# CH32V205CCT-R0.net
KiCad netlist of a schematic drawn in Altium Designer
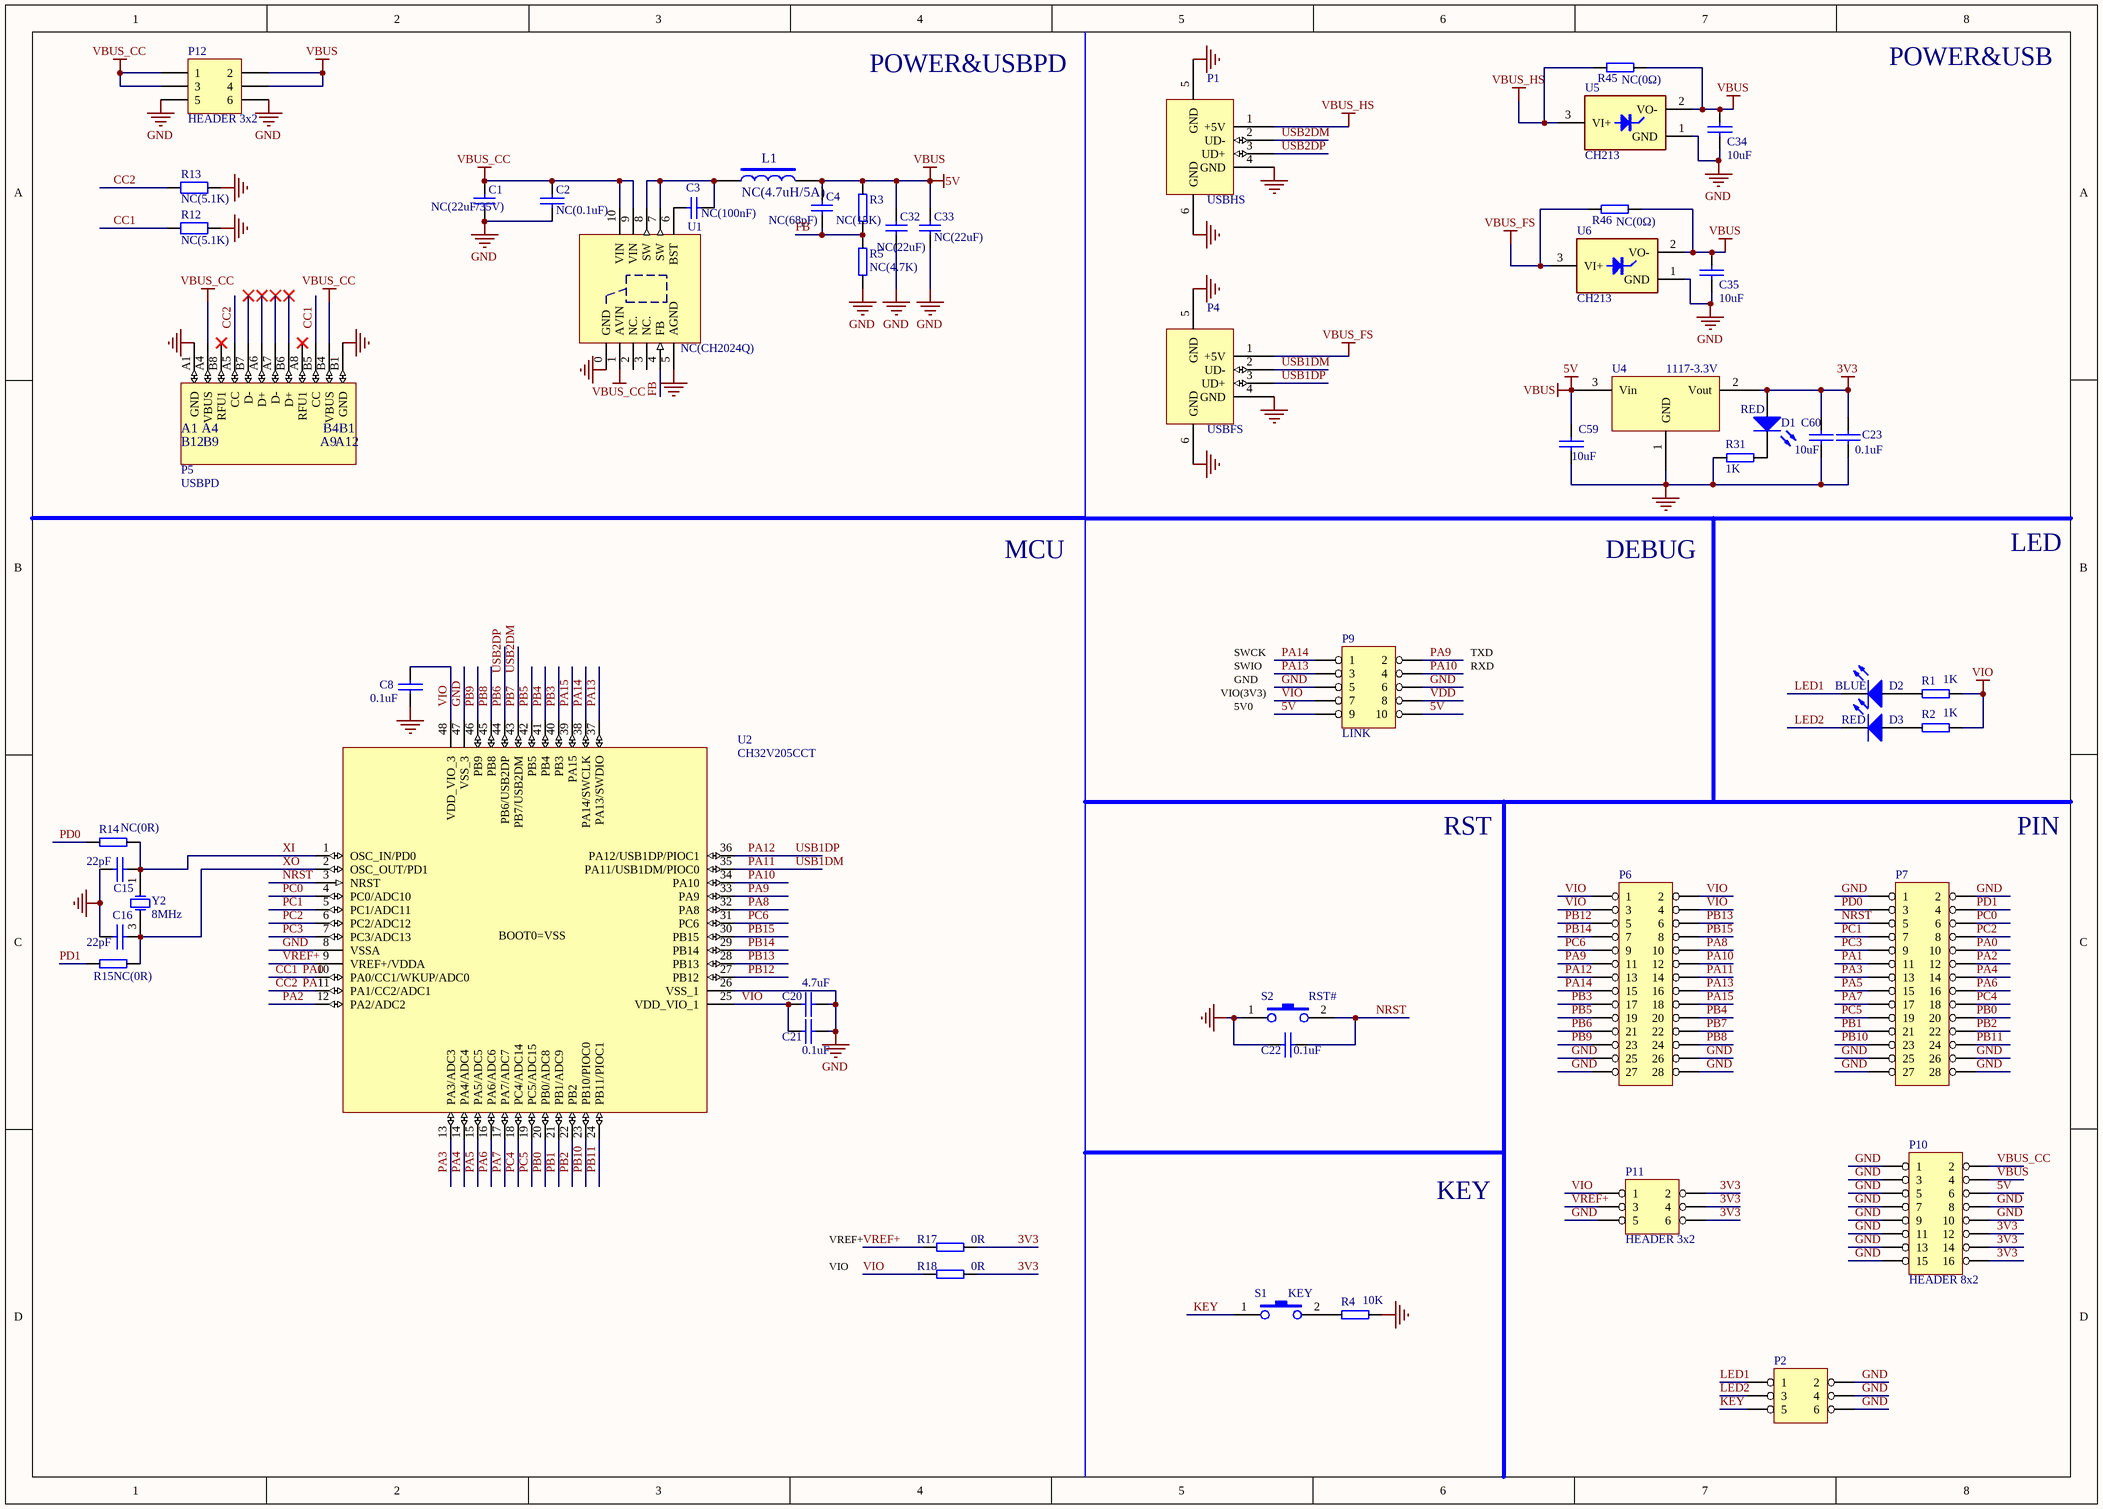
[diagram p0: CH32V205CCT-R0.SchDoc]

(export (version "E")
  (design (tool "Eeschema 10.0.6"))
  (components
    (comp (ref "C1")
      (value "NC(22uF/35V)")
      (footprint "0805_C")
      (description "贴片电容")
      (libsource (lib "Miscellaneous Devices LC") (part "0603 100nF (104) 10% 50V"))
    )
    (comp (ref "C2")
      (value "NC(0.1uF)")
      (footprint "0402_C")
      (description "Capacitor")
      (libsource (lib "*") (part "CAP"))
    )
    (comp (ref "C3")
      (value "NC(100nF)")
      (footprint "0603_C")
      (description "贴片电容")
      (libsource (lib "Miscellaneous Devices LC") (part "0603 1uF (105) 10% 50V"))
    )
    (comp (ref "C4")
      (value "NC(68pF)")
      (footprint "0402_C")
      (description "贴片电容")
      (libsource (lib "Miscellaneous Devices LC") (part "0603 100nF (104) 10% 50V"))
    )
    (comp (ref "C8")
      (value "0.1uF")
      (footprint "0603_C")
      (description "Capacitor")
      (libsource (lib "*") (part "CAP"))
    )
    (comp (ref "C15")
      (value "22pF")
      (footprint "0603_C")
      (description "Capacitor")
      (libsource (lib "*") (part "CAP"))
    )
    (comp (ref "C16")
      (value "22pF")
      (footprint "0603_C")
      (description "Capacitor")
      (libsource (lib "*") (part "CAP"))
    )
    (comp (ref "C20")
      (value "4.7uF")
      (footprint "0603_C")
      (description "Capacitor")
      (libsource (lib "*") (part "CAP"))
    )
    (comp (ref "C21")
      (value "0.1uF")
      (footprint "0603_C")
      (description "Capacitor")
      (libsource (lib "*") (part "CAP"))
    )
    (comp (ref "C22")
      (value "0.1uF")
      (footprint "0603_C")
      (description "Capacitor")
      (libsource (lib "") (part "CAP_1"))
    )
    (comp (ref "C23")
      (value "0.1uF")
      (footprint "0402_C")
      (description "Capacitor")
      (libsource (lib "*") (part "CAP"))
    )
    (comp (ref "C32")
      (value "NC(22uF)")
      (footprint "0805_C")
      (description "贴片电容")
      (libsource (lib "Miscellaneous Devices LC") (part "0603 100nF (104) 10% 50V"))
    )
    (comp (ref "C33")
      (value "NC(22uF)")
      (footprint "0805_C")
      (description "贴片电容")
      (libsource (lib "Miscellaneous Devices LC") (part "0603 100nF (104) 10% 50V"))
    )
    (comp (ref "C34")
      (value "10uF")
      (footprint "0603_C")
      (description "Capacitor")
      (libsource (lib "") (part "CAP_1"))
    )
    (comp (ref "C35")
      (value "10uF")
      (footprint "0603_C")
      (description "Capacitor")
      (libsource (lib "") (part "CAP_1"))
    )
    (comp (ref "C59")
      (value "10uF")
      (footprint "0603_C")
      (description "Capacitor")
      (libsource (lib "*") (part "CAP"))
    )
    (comp (ref "C60")
      (value "10uF")
      (footprint "0603_C")
      (description "Capacitor")
      (libsource (lib "*") (part "CAP"))
    )
    (comp (ref "D1")
      (value "RED")
      (footprint "0603+")
      (description "Typical INFRARED GaAs LED")
      (fields (field (name "PUBLISHER") "Altium Limited"))
      (libsource (lib "*") (part "LED0"))
    )
    (comp (ref "D2")
      (value "BLUE")
      (footprint "0603+")
      (description "Typical INFRARED GaAs LED")
      (fields (field (name "PUBLISHER") "Altium Limited"))
      (libsource (lib "*") (part "LED0"))
    )
    (comp (ref "D3")
      (value "RED")
      (footprint "0603+")
      (description "Typical INFRARED GaAs LED")
      (fields (field (name "PUBLISHER") "Altium Limited"))
      (libsource (lib "*") (part "LED0"))
    )
    (comp (ref "L1")
      (value "NC(4.7uH/5A)")
      (footprint "SMD_6x6mm")
      (libsource (lib "wch_sch_others") (part "INDUCTOR"))
    )
    (comp (ref "P1")
      (value "USBHS")
      (footprint "USBAF")
      (description "USB Port")
      (libsource (lib "*") (part "USB"))
    )
    (comp (ref "P2")
      (value "IO")
      (footprint "MYPCB:IDC6-2.54mm")
      (description "Header, 3-Pin, Dual row")
      (libsource (lib "") (part "HEADER 3x2_1"))
    )
    (comp (ref "P4")
      (value "USBFS")
      (footprint "USBAF")
      (description "USB Port")
      (libsource (lib "*") (part "USB"))
    )
    (comp (ref "P5")
      (value "USBPD")
      (footprint "TYPE-C-Receptacle-2.0")
      (libsource (lib "*") (part "TYPE-C1"))
    )
    (comp (ref "P6")
      (value "~")
      (footprint "MYPCB:IDC28-2.54MM")
      (description "Header, 14-Pin, Dual row")
      (libsource (lib "wch_sch_others") (part "HEADER 14x2"))
    )
    (comp (ref "P7")
      (value "~")
      (footprint "MYPCB:IDC28-2.54MM")
      (description "Header, 14-Pin, Dual row")
      (libsource (lib "wch_sch_others") (part "HEADER 14x2"))
    )
    (comp (ref "P9")
      (value "LINK")
      (footprint "MYPCB:IDC10-2.54mm")
      (description "Header, 5-Pin, Dual row")
      (libsource (lib "wch_sch_others") (part "HEADER 5x2"))
    )
    (comp (ref "P10")
      (value "HEADER 8x2")
      (footprint "MYPCB:IDC16-2.54mm")
      (description "Header, 8-Pin, Dual row")
      (libsource (lib "wch_sch_others") (part "HEADER 8x2"))
    )
    (comp (ref "P11")
      (value "HEADER 3x2")
      (footprint "MYPCB:IDC6-2.54mm")
      (description "Header, 3-Pin, Dual row")
      (libsource (lib "") (part "HEADER 3x2_1"))
    )
    (comp (ref "P12")
      (value "HEADER 3x2")
      (footprint "MYPCB:IDC6-2.54mm")
      (description "Header, 3-Pin, Dual row")
      (libsource (lib "wch_sch_others") (part "HEADER 3x2"))
    )
    (comp (ref "R1") (value "1K") (footprint "CHXXX:0603") (libsource (lib "wch_sch_others") (part "RES")))
    (comp (ref "R2") (value "1K") (footprint "CHXXX:0603") (libsource (lib "wch_sch_others") (part "RES")))
    (comp (ref "R3") (value "NC(15K)") (footprint "0402") (libsource (lib "wch_sch_others(1)") (part "RES")))
    (comp (ref "R4") (value "10K") (footprint "CHXXX:0603") (libsource (lib "wch_sch_others") (part "RES")))
    (comp (ref "R5") (value "NC(4.7K)") (footprint "0402") (libsource (lib "wch_sch_others(1)") (part "RES")))
    (comp (ref "R12")
      (value "NC(5.1K)")
      (footprint "0402")
      (description "Resistor")
      (libsource (lib "Miscellaneous Devices") (part "Res2"))
    )
    (comp (ref "R13")
      (value "NC(5.1K)")
      (footprint "0402")
      (description "Resistor")
      (libsource (lib "Miscellaneous Devices") (part "Res2"))
    )
    (comp (ref "R14")
      (value "NC(0R)")
      (footprint "CHXXX:0603")
      (libsource (lib "wch_sch_others") (part "RES"))
    )
    (comp (ref "R15")
      (value "NC(0R)")
      (footprint "CHXXX:0603")
      (libsource (lib "wch_sch_others") (part "RES"))
    )
    (comp (ref "R17") (value "0R") (footprint "CHXXX:0603") (libsource (lib "*") (part "R")))
    (comp (ref "R18") (value "0R") (footprint "CHXXX:0603") (libsource (lib "*") (part "R")))
    (comp (ref "R31") (value "1K") (footprint "0402") (libsource (lib "wch_sch_others") (part "RES")))
    (comp (ref "R45") (value "NC(0Ω)") (footprint "0402") (libsource (lib "wch_sch_others") (part "RES")))
    (comp (ref "R46") (value "NC(0Ω)") (footprint "0402") (libsource (lib "wch_sch_others") (part "RES")))
    (comp (ref "S1")
      (value "KEY")
      (footprint "SMD_6.1x3.65x2.5mm-KEY")
      (libsource (lib "wch_sch_others") (part "KEY1"))
    )
    (comp (ref "S2")
      (value "RST#")
      (footprint "SMD_6.1x3.65x2.5mm-KEY")
      (libsource (lib "wch_sch_others") (part "KEY1"))
    )
    (comp (ref "U1")
      (value "NC(CH2024Q)")
      (footprint "DFN10_3X3")
      (description "Step-Down DC-DC Converter, 28V input, FB 1.2V, 3A output")
      (libsource (lib "DHXXXSCH") (part "CH2024Q"))
    )
    (comp (ref "U2")
      (value "CH32V205CCT")
      (footprint "LQFP48")
      (description "RISC-V MCU, 192MHz, USB_480M, USB FS, PD, PIOC, ADC, TKEY, 2*OPA, 2*CMP")
      (libsource (lib "CHXXX") (part "CH32V205CCT"))
    )
    (comp (ref "U4")
      (value "1117-3.3V")
      (footprint "SOT-223")
      (libsource (lib "wch_sch_others") (part "1117-3.3V"))
    )
    (comp (ref "U5")
      (value "CH213")
      (footprint "SOT-23-3")
      (description "Ideal Diode 5V*1A")
      (libsource (lib "CHXXX") (part "CH213E"))
    )
    (comp (ref "U6")
      (value "CH213")
      (footprint "SOT-23-3")
      (description "Ideal Diode 5V*1A")
      (libsource (lib "CHXXX") (part "CH213E"))
    )
    (comp (ref "Y2")
      (value "8MHz")
      (footprint "XT3225")
      (description "Crystal Oscillator")
      (fields (field (name "PUBLISHER") "Altium Limited"))
      (libsource (lib "*") (part "XTAL"))
    )
  )
  (nets
    (net (code "2") (name "/CC1") (class "Default")
      (node (ref "P5") (pin "B5") (pinfunction "CC_B5") (pintype "bidirectional"))
      (node (ref "P7") (pin "10") (pinfunction "10_10") (pintype "passive"))
      (node (ref "R12") (pin "1") (pinfunction "1_1") (pintype "passive"))
      (node (ref "U2") (pin "10") (pinfunction "PA0/CC1/WKUP/ADC0_10") (pintype "bidirectional"))
    )
    (net (code "3") (name "/CC2") (class "Default")
      (node (ref "P5") (pin "A5") (pinfunction "CC_A5") (pintype "bidirectional"))
      (node (ref "P7") (pin "11") (pinfunction "11_11") (pintype "passive"))
      (node (ref "R13") (pin "1") (pinfunction "1_1") (pintype "passive"))
      (node (ref "U2") (pin "11") (pinfunction "PA1/CC2/ADC1_11") (pintype "bidirectional"))
    )
    (net (code "4") (name "/FB") (class "Default")
      (node (ref "C4") (pin "2") (pinfunction "2_2") (pintype "passive"))
      (node (ref "R3") (pin "1") (pintype "passive"))
      (node (ref "R5") (pin "2") (pintype "passive"))
      (node (ref "U1") (pin "4") (pinfunction "FB_4") (pintype "input"))
    )
    (net (code "5") (name "/KEY") (class "Default")
      (node (ref "P2") (pin "5") (pinfunction "5_5") (pintype "passive"))
      (node (ref "S1") (pin "1") (pinfunction "1_1") (pintype "passive"))
    )
    (net (code "6") (name "/LED1") (class "Default")
      (node (ref "D2") (pin "2") (pinfunction "K_2") (pintype "passive"))
      (node (ref "P2") (pin "1") (pinfunction "1_1") (pintype "passive"))
    )
    (net (code "7") (name "/LED2") (class "Default")
      (node (ref "D3") (pin "2") (pinfunction "K_2") (pintype "passive"))
      (node (ref "P2") (pin "3") (pinfunction "3_3") (pintype "passive"))
    )
    (net (code "8") (name "/NRST") (class "Default")
      (node (ref "C22") (pin "2") (pinfunction "2_2") (pintype "passive"))
      (node (ref "P7") (pin "5") (pinfunction "5_5") (pintype "passive"))
      (node (ref "S2") (pin "2") (pinfunction "2_2") (pintype "passive"))
      (node (ref "U2") (pin "3") (pinfunction "NRST_3") (pintype "input"))
    )
    (net (code "9") (name "/PA2") (class "Default")
      (node (ref "P7") (pin "12") (pinfunction "12_12") (pintype "passive"))
      (node (ref "U2") (pin "12") (pinfunction "PA2/ADC2_12") (pintype "bidirectional"))
    )
    (net (code "10") (name "/PA3") (class "Default")
      (node (ref "P7") (pin "13") (pinfunction "13_13") (pintype "passive"))
      (node (ref "U2") (pin "13") (pinfunction "PA3/ADC3_13") (pintype "bidirectional"))
    )
    (net (code "11") (name "/PA4") (class "Default")
      (node (ref "P7") (pin "14") (pinfunction "14_14") (pintype "passive"))
      (node (ref "U2") (pin "14") (pinfunction "PA4/ADC4_14") (pintype "bidirectional"))
    )
    (net (code "12") (name "/PA5") (class "Default")
      (node (ref "P7") (pin "15") (pinfunction "15_15") (pintype "passive"))
      (node (ref "U2") (pin "15") (pinfunction "PA5/ADC5_15") (pintype "bidirectional"))
    )
    (net (code "13") (name "/PA6") (class "Default")
      (node (ref "P7") (pin "16") (pinfunction "16_16") (pintype "passive"))
      (node (ref "U2") (pin "16") (pinfunction "PA6/ADC6_16") (pintype "bidirectional"))
    )
    (net (code "14") (name "/PA7") (class "Default")
      (node (ref "P7") (pin "17") (pinfunction "17_17") (pintype "passive"))
      (node (ref "U2") (pin "17") (pinfunction "PA7/ADC7_17") (pintype "bidirectional"))
    )
    (net (code "15") (name "/PA8") (class "Default")
      (node (ref "P6") (pin "10") (pinfunction "10_10") (pintype "passive"))
      (node (ref "U2") (pin "32") (pinfunction "PA8_32") (pintype "bidirectional"))
    )
    (net (code "16") (name "/PA9") (class "Default")
      (node (ref "P6") (pin "11") (pinfunction "11_11") (pintype "passive"))
      (node (ref "P9") (pin "2") (pinfunction "2_2") (pintype "passive"))
      (node (ref "U2") (pin "33") (pinfunction "PA9_33") (pintype "bidirectional"))
    )
    (net (code "17") (name "/PA10") (class "Default")
      (node (ref "P6") (pin "12") (pinfunction "12_12") (pintype "passive"))
      (node (ref "P9") (pin "4") (pinfunction "4_4") (pintype "passive"))
      (node (ref "U2") (pin "34") (pinfunction "PA10_34") (pintype "bidirectional"))
    )
    (net (code "18") (name "/PA11") (class "Default")
      (node (ref "P4") (pin "2") (pinfunction "UD-_2") (pintype "bidirectional"))
      (node (ref "P6") (pin "14") (pinfunction "14_14") (pintype "passive"))
      (node (ref "U2") (pin "35") (pinfunction "PA11/USB1DM/PIOC0_35") (pintype "bidirectional"))
    )
    (net (code "19") (name "/PA12") (class "Default")
      (node (ref "P4") (pin "3") (pinfunction "UD+_3") (pintype "bidirectional"))
      (node (ref "P6") (pin "13") (pinfunction "13_13") (pintype "passive"))
      (node (ref "U2") (pin "36") (pinfunction "PA12/USB1DP/PIOC1_36") (pintype "bidirectional"))
    )
    (net (code "20") (name "/PA13") (class "Default")
      (node (ref "P6") (pin "16") (pinfunction "16_16") (pintype "passive"))
      (node (ref "P9") (pin "3") (pinfunction "3_3") (pintype "passive"))
      (node (ref "U2") (pin "37") (pinfunction "PA13/SWDIO_37") (pintype "bidirectional"))
    )
    (net (code "21") (name "/PA14") (class "Default")
      (node (ref "P6") (pin "15") (pinfunction "15_15") (pintype "passive"))
      (node (ref "P9") (pin "1") (pinfunction "1_1") (pintype "passive"))
      (node (ref "U2") (pin "38") (pinfunction "PA14/SWCLK_38") (pintype "bidirectional"))
    )
    (net (code "22") (name "/PA15") (class "Default")
      (node (ref "P6") (pin "18") (pinfunction "18_18") (pintype "passive"))
      (node (ref "U2") (pin "39") (pinfunction "PA15_39") (pintype "bidirectional"))
    )
    (net (code "23") (name "/PB0") (class "Default")
      (node (ref "P7") (pin "20") (pinfunction "20_20") (pintype "passive"))
      (node (ref "U2") (pin "20") (pinfunction "PB0/ADC8_20") (pintype "bidirectional"))
    )
    (net (code "24") (name "/PB1") (class "Default")
      (node (ref "P7") (pin "21") (pinfunction "21_21") (pintype "passive"))
      (node (ref "U2") (pin "21") (pinfunction "PB1/ADC9_21") (pintype "bidirectional"))
    )
    (net (code "25") (name "/PB2") (class "Default")
      (node (ref "P7") (pin "22") (pinfunction "22_22") (pintype "passive"))
      (node (ref "U2") (pin "22") (pinfunction "PB2_22") (pintype "bidirectional"))
    )
    (net (code "26") (name "/PB3") (class "Default")
      (node (ref "P6") (pin "17") (pinfunction "17_17") (pintype "passive"))
      (node (ref "U2") (pin "40") (pinfunction "PB3_40") (pintype "bidirectional"))
    )
    (net (code "27") (name "/PB4") (class "Default")
      (node (ref "P6") (pin "20") (pinfunction "20_20") (pintype "passive"))
      (node (ref "U2") (pin "41") (pinfunction "PB4_41") (pintype "bidirectional"))
    )
    (net (code "28") (name "/PB5") (class "Default")
      (node (ref "P6") (pin "19") (pinfunction "19_19") (pintype "passive"))
      (node (ref "U2") (pin "42") (pinfunction "PB5_42") (pintype "bidirectional"))
    )
    (net (code "29") (name "/PB6") (class "Default")
      (node (ref "P1") (pin "3") (pinfunction "UD+_3") (pintype "bidirectional"))
      (node (ref "P6") (pin "21") (pinfunction "21_21") (pintype "passive"))
      (node (ref "U2") (pin "44") (pinfunction "PB6/USB2DP_44") (pintype "bidirectional"))
    )
    (net (code "30") (name "/PB7") (class "Default")
      (node (ref "P1") (pin "2") (pinfunction "UD-_2") (pintype "bidirectional"))
      (node (ref "P6") (pin "22") (pinfunction "22_22") (pintype "passive"))
      (node (ref "U2") (pin "43") (pinfunction "PB7/USB2DM_43") (pintype "bidirectional"))
    )
    (net (code "31") (name "/PB8") (class "Default")
      (node (ref "P6") (pin "24") (pinfunction "24_24") (pintype "passive"))
      (node (ref "U2") (pin "45") (pinfunction "PB8_45") (pintype "bidirectional"))
    )
    (net (code "32") (name "/PB9") (class "Default")
      (node (ref "P6") (pin "23") (pinfunction "23_23") (pintype "passive"))
      (node (ref "U2") (pin "46") (pinfunction "PB9_46") (pintype "bidirectional"))
    )
    (net (code "33") (name "/PB10") (class "Default")
      (node (ref "P7") (pin "23") (pinfunction "23_23") (pintype "passive"))
      (node (ref "U2") (pin "23") (pinfunction "PB10/PIOC0_23") (pintype "bidirectional"))
    )
    (net (code "34") (name "/PB11") (class "Default")
      (node (ref "P7") (pin "24") (pinfunction "24_24") (pintype "passive"))
      (node (ref "U2") (pin "24") (pinfunction "PB11/PIOC1_24") (pintype "bidirectional"))
    )
    (net (code "35") (name "/PB12") (class "Default")
      (node (ref "P6") (pin "5") (pinfunction "5_5") (pintype "passive"))
      (node (ref "U2") (pin "27") (pinfunction "PB12_27") (pintype "bidirectional"))
    )
    (net (code "36") (name "/PB13") (class "Default")
      (node (ref "P6") (pin "6") (pinfunction "6_6") (pintype "passive"))
      (node (ref "U2") (pin "28") (pinfunction "PB13_28") (pintype "bidirectional"))
    )
    (net (code "37") (name "/PB14") (class "Default")
      (node (ref "P6") (pin "7") (pinfunction "7_7") (pintype "passive"))
      (node (ref "U2") (pin "29") (pinfunction "PB14_29") (pintype "bidirectional"))
    )
    (net (code "38") (name "/PB15") (class "Default")
      (node (ref "P6") (pin "8") (pinfunction "8_8") (pintype "passive"))
      (node (ref "U2") (pin "30") (pinfunction "PB15_30") (pintype "bidirectional"))
    )
    (net (code "39") (name "/PC0") (class "Default")
      (node (ref "P7") (pin "6") (pinfunction "6_6") (pintype "passive"))
      (node (ref "U2") (pin "4") (pinfunction "PC0/ADC10_4") (pintype "bidirectional"))
    )
    (net (code "40") (name "/PC1") (class "Default")
      (node (ref "P7") (pin "7") (pinfunction "7_7") (pintype "passive"))
      (node (ref "U2") (pin "5") (pinfunction "PC1/ADC11_5") (pintype "bidirectional"))
    )
    (net (code "41") (name "/PC2") (class "Default")
      (node (ref "P7") (pin "8") (pinfunction "8_8") (pintype "passive"))
      (node (ref "U2") (pin "6") (pinfunction "PC2/ADC12_6") (pintype "bidirectional"))
    )
    (net (code "42") (name "/PC3") (class "Default")
      (node (ref "P7") (pin "9") (pinfunction "9_9") (pintype "passive"))
      (node (ref "U2") (pin "7") (pinfunction "PC3/ADC13_7") (pintype "bidirectional"))
    )
    (net (code "43") (name "/PC4") (class "Default")
      (node (ref "P7") (pin "18") (pinfunction "18_18") (pintype "passive"))
      (node (ref "U2") (pin "18") (pinfunction "PC4/ADC14_18") (pintype "bidirectional"))
    )
    (net (code "44") (name "/PC5") (class "Default")
      (node (ref "P7") (pin "19") (pinfunction "19_19") (pintype "passive"))
      (node (ref "U2") (pin "19") (pinfunction "PC5/ADC15_19") (pintype "bidirectional"))
    )
    (net (code "45") (name "/PC6") (class "Default")
      (node (ref "P6") (pin "9") (pinfunction "9_9") (pintype "passive"))
      (node (ref "U2") (pin "31") (pinfunction "PC6_31") (pintype "bidirectional"))
    )
    (net (code "46") (name "/PD0") (class "Default")
      (node (ref "P7") (pin "3") (pinfunction "3_3") (pintype "passive"))
      (node (ref "R14") (pin "1") (pintype "passive"))
    )
    (net (code "47") (name "/PD1") (class "Default")
      (node (ref "P7") (pin "4") (pinfunction "4_4") (pintype "passive"))
      (node (ref "R15") (pin "1") (pintype "passive"))
    )
    (net (code "48") (name "/VDD") (class "Default")
      (node (ref "P9") (pin "8") (pinfunction "8_8") (pintype "passive"))
    )
    (net (code "49") (name "/VREF+") (class "Default")
      (node (ref "P11") (pin "3") (pinfunction "3_3") (pintype "passive"))
      (node (ref "R17") (pin "2") (pinfunction "2_2") (pintype "passive"))
      (node (ref "U2") (pin "9") (pinfunction "VREF+/VDDA_9") (pintype "power_in"))
    )
    (net (code "50") (name "/XI") (class "Default")
      (node (ref "C15") (pin "2") (pinfunction "2_2") (pintype "passive"))
      (node (ref "R14") (pin "2") (pintype "passive"))
      (node (ref "U2") (pin "1") (pinfunction "OSC_IN/PD0_1") (pintype "bidirectional"))
      (node (ref "Y2") (pin "1") (pinfunction "OSC1_1") (pintype "passive"))
    )
    (net (code "51") (name "/XO") (class "Default")
      (node (ref "C16") (pin "2") (pinfunction "2_2") (pintype "passive"))
      (node (ref "R15") (pin "2") (pintype "passive"))
      (node (ref "U2") (pin "2") (pinfunction "OSC_OUT/PD1_2") (pintype "bidirectional"))
      (node (ref "Y2") (pin "3") (pinfunction "OSC2_3") (pintype "passive"))
    )
    (net (code "52") (name "3V3") (class "Default")
      (node (ref "C23") (pin "1") (pinfunction "1_1") (pintype "passive"))
      (node (ref "C60") (pin "1") (pinfunction "1_1") (pintype "passive"))
      (node (ref "D1") (pin "1") (pinfunction "A_1") (pintype "passive"))
      (node (ref "P10") (pin "12") (pinfunction "12_12") (pintype "passive"))
      (node (ref "P10") (pin "14") (pinfunction "14_14") (pintype "passive"))
      (node (ref "P10") (pin "16") (pinfunction "16_16") (pintype "passive"))
      (node (ref "P11") (pin "2") (pinfunction "2_2") (pintype "passive"))
      (node (ref "P11") (pin "4") (pinfunction "4_4") (pintype "passive"))
      (node (ref "P11") (pin "6") (pinfunction "6_6") (pintype "passive"))
      (node (ref "R17") (pin "1") (pinfunction "1_1") (pintype "passive"))
      (node (ref "R18") (pin "1") (pinfunction "1_1") (pintype "passive"))
      (node (ref "U4") (pin "2") (pinfunction "Vout_2") (pintype "passive"))
    )
    (net (code "53") (name "5V") (class "Default")
      (node (ref "C32") (pin "2") (pinfunction "2_2") (pintype "passive"))
      (node (ref "C33") (pin "2") (pinfunction "2_2") (pintype "passive"))
      (node (ref "C34") (pin "1") (pinfunction "1_1") (pintype "passive"))
      (node (ref "C35") (pin "1") (pinfunction "1_1") (pintype "passive"))
      (node (ref "C4") (pin "1") (pinfunction "1_1") (pintype "passive"))
      (node (ref "C59") (pin "1") (pinfunction "1_1") (pintype "passive"))
      (node (ref "L1") (pin "2") (pinfunction "2_2") (pintype "passive"))
      (node (ref "P10") (pin "4") (pinfunction "4_4") (pintype "passive"))
      (node (ref "P10") (pin "6") (pinfunction "6_6") (pintype "passive"))
      (node (ref "P12") (pin "2") (pinfunction "2_2") (pintype "passive"))
      (node (ref "P12") (pin "4") (pinfunction "4_4") (pintype "passive"))
      (node (ref "P9") (pin "10") (pinfunction "10_10") (pintype "passive"))
      (node (ref "P9") (pin "9") (pinfunction "9_9") (pintype "passive"))
      (node (ref "R3") (pin "2") (pintype "passive"))
      (node (ref "R45") (pin "1") (pintype "passive"))
      (node (ref "R46") (pin "1") (pintype "passive"))
      (node (ref "U4") (pin "3") (pinfunction "Vin_3") (pintype "passive"))
      (node (ref "U5") (pin "2") (pinfunction "VO-_2") (pintype "power_in"))
      (node (ref "U6") (pin "2") (pinfunction "VO-_2") (pintype "power_in"))
    )
    (net (code "54") (name "GND") (class "Default")
      (node (ref "C1") (pin "1") (pinfunction "1_1") (pintype "passive"))
      (node (ref "C15") (pin "1") (pinfunction "1_1") (pintype "passive"))
      (node (ref "C16") (pin "1") (pinfunction "1_1") (pintype "passive"))
      (node (ref "C2") (pin "1") (pinfunction "1_1") (pintype "passive"))
      (node (ref "C20") (pin "1") (pinfunction "1_1") (pintype "passive"))
      (node (ref "C21") (pin "1") (pinfunction "1_1") (pintype "passive"))
      (node (ref "C22") (pin "1") (pinfunction "1_1") (pintype "passive"))
      (node (ref "C23") (pin "2") (pinfunction "2_2") (pintype "passive"))
      (node (ref "C32") (pin "1") (pinfunction "1_1") (pintype "passive"))
      (node (ref "C33") (pin "1") (pinfunction "1_1") (pintype "passive"))
      (node (ref "C34") (pin "2") (pinfunction "2_2") (pintype "passive"))
      (node (ref "C35") (pin "2") (pinfunction "2_2") (pintype "passive"))
      (node (ref "C59") (pin "2") (pinfunction "2_2") (pintype "passive"))
      (node (ref "C60") (pin "2") (pinfunction "2_2") (pintype "passive"))
      (node (ref "C8") (pin "1") (pinfunction "1_1") (pintype "passive"))
      (node (ref "P1") (pin "4") (pinfunction "GND_4") (pintype "power_in"))
      (node (ref "P1") (pin "5") (pinfunction "GND_5") (pintype "power_in"))
      (node (ref "P1") (pin "6") (pinfunction "GND_6") (pintype "power_in"))
      (node (ref "P10") (pin "1") (pinfunction "1_1") (pintype "passive"))
      (node (ref "P10") (pin "10") (pinfunction "10_10") (pintype "passive"))
      (node (ref "P10") (pin "11") (pinfunction "11_11") (pintype "passive"))
      (node (ref "P10") (pin "13") (pinfunction "13_13") (pintype "passive"))
      (node (ref "P10") (pin "15") (pinfunction "15_15") (pintype "passive"))
      (node (ref "P10") (pin "3") (pinfunction "3_3") (pintype "passive"))
      (node (ref "P10") (pin "5") (pinfunction "5_5") (pintype "passive"))
      (node (ref "P10") (pin "7") (pinfunction "7_7") (pintype "passive"))
      (node (ref "P10") (pin "8") (pinfunction "8_8") (pintype "passive"))
      (node (ref "P10") (pin "9") (pinfunction "9_9") (pintype "passive"))
      (node (ref "P11") (pin "5") (pinfunction "5_5") (pintype "passive"))
      (node (ref "P12") (pin "5") (pinfunction "5_5") (pintype "passive"))
      (node (ref "P12") (pin "6") (pinfunction "6_6") (pintype "passive"))
      (node (ref "P2") (pin "2") (pinfunction "2_2") (pintype "passive"))
      (node (ref "P2") (pin "4") (pinfunction "4_4") (pintype "passive"))
      (node (ref "P2") (pin "6") (pinfunction "6_6") (pintype "passive"))
      (node (ref "P4") (pin "4") (pinfunction "GND_4") (pintype "power_in"))
      (node (ref "P4") (pin "5") (pinfunction "GND_5") (pintype "power_in"))
      (node (ref "P4") (pin "6") (pinfunction "GND_6") (pintype "power_in"))
      (node (ref "P5") (pin "A1") (pinfunction "GND_A1") (pintype "bidirectional"))
      (node (ref "P5") (pin "B1") (pinfunction "GND_B1") (pintype "bidirectional"))
      (node (ref "P6") (pin "25") (pinfunction "25_25") (pintype "passive"))
      (node (ref "P6") (pin "26") (pinfunction "26_26") (pintype "passive"))
      (node (ref "P6") (pin "27") (pinfunction "27_27") (pintype "passive"))
      (node (ref "P6") (pin "28") (pinfunction "28_28") (pintype "passive"))
      (node (ref "P7") (pin "1") (pinfunction "1_1") (pintype "passive"))
      (node (ref "P7") (pin "2") (pinfunction "2_2") (pintype "passive"))
      (node (ref "P7") (pin "25") (pinfunction "25_25") (pintype "passive"))
      (node (ref "P7") (pin "26") (pinfunction "26_26") (pintype "passive"))
      (node (ref "P7") (pin "27") (pinfunction "27_27") (pintype "passive"))
      (node (ref "P7") (pin "28") (pinfunction "28_28") (pintype "passive"))
      (node (ref "P9") (pin "5") (pinfunction "5_5") (pintype "passive"))
      (node (ref "P9") (pin "6") (pinfunction "6_6") (pintype "passive"))
      (node (ref "R12") (pin "2") (pinfunction "2_2") (pintype "passive"))
      (node (ref "R13") (pin "2") (pinfunction "2_2") (pintype "passive"))
      (node (ref "R31") (pin "1") (pintype "passive"))
      (node (ref "R4") (pin "1") (pintype "passive"))
      (node (ref "R5") (pin "1") (pintype "passive"))
      (node (ref "S2") (pin "1") (pinfunction "1_1") (pintype "passive"))
      (node (ref "U1") (pin "0") (pinfunction "GND_0") (pintype "power_in"))
      (node (ref "U1") (pin "5") (pinfunction "AGND_5") (pintype "power_in"))
      (node (ref "U2") (pin "26") (pinfunction "VSS_1_26") (pintype "power_in"))
      (node (ref "U2") (pin "47") (pinfunction "VSS_3_47") (pintype "power_in"))
      (node (ref "U2") (pin "8") (pinfunction "VSSA_8") (pintype "power_in"))
      (node (ref "U4") (pin "1") (pinfunction "GND_1") (pintype "passive"))
      (node (ref "U5") (pin "1") (pinfunction "GND_1") (pintype "power_in"))
      (node (ref "U6") (pin "1") (pinfunction "GND_1") (pintype "power_in"))
    )
    (net (code "55") (name "Net-(C3-Pad2)") (class "Default")
      (node (ref "C3") (pin "2") (pinfunction "2_2") (pintype "passive"))
      (node (ref "L1") (pin "1") (pinfunction "1_1") (pintype "passive"))
      (node (ref "U1") (pin "7") (pinfunction "SW_7") (pintype "output"))
      (node (ref "U1") (pin "8") (pinfunction "SW_8") (pintype "output"))
    )
    (net (code "56") (name "Net-(D1-K)") (class "Default")
      (node (ref "D1") (pin "2") (pinfunction "K_2") (pintype "passive"))
      (node (ref "R31") (pin "2") (pintype "passive"))
    )
    (net (code "57") (name "Net-(D2-A)") (class "Default")
      (node (ref "D2") (pin "1") (pinfunction "A_1") (pintype "passive"))
      (node (ref "R1") (pin "2") (pintype "passive"))
    )
    (net (code "58") (name "Net-(D3-A)") (class "Default")
      (node (ref "D3") (pin "1") (pinfunction "A_1") (pintype "passive"))
      (node (ref "R2") (pin "2") (pintype "passive"))
    )
    (net (code "59") (name "Net-(R4-Pad2)") (class "Default")
      (node (ref "R4") (pin "2") (pintype "passive"))
      (node (ref "S1") (pin "2") (pinfunction "2_2") (pintype "passive"))
    )
    (net (code "60") (name "Net-(U1-BST)") (class "Default")
      (node (ref "C3") (pin "1") (pinfunction "1_1") (pintype "passive"))
      (node (ref "U1") (pin "6") (pinfunction "BST_6") (pintype "power_in"))
    )
    (net (code "61") (name "VBUS_CC") (class "Default")
      (node (ref "C1") (pin "2") (pinfunction "2_2") (pintype "passive"))
      (node (ref "C2") (pin "2") (pinfunction "2_2") (pintype "passive"))
      (node (ref "P10") (pin "2") (pinfunction "2_2") (pintype "passive"))
      (node (ref "P12") (pin "1") (pinfunction "1_1") (pintype "passive"))
      (node (ref "P12") (pin "3") (pinfunction "3_3") (pintype "passive"))
      (node (ref "P5") (pin "A4") (pinfunction "VBUS_A4") (pintype "bidirectional"))
      (node (ref "P5") (pin "B4") (pinfunction "VBUS_B4") (pintype "bidirectional"))
      (node (ref "U1") (pin "1") (pinfunction "AVIN_1") (pintype "power_in"))
      (node (ref "U1") (pin "10") (pinfunction "VIN_10") (pintype "power_in"))
      (node (ref "U1") (pin "9") (pinfunction "VIN_9") (pintype "power_in"))
    )
    (net (code "62") (name "VBUS_FS") (class "Default")
      (node (ref "P4") (pin "1") (pinfunction "+5V_1") (pintype "power_in"))
      (node (ref "R46") (pin "2") (pintype "passive"))
      (node (ref "U6") (pin "3") (pinfunction "VI+_3") (pintype "power_in"))
    )
    (net (code "63") (name "VBUS_HS") (class "Default")
      (node (ref "P1") (pin "1") (pinfunction "+5V_1") (pintype "power_in"))
      (node (ref "R45") (pin "2") (pintype "passive"))
      (node (ref "U5") (pin "3") (pinfunction "VI+_3") (pintype "power_in"))
    )
    (net (code "64") (name "VIO") (class "Default")
      (node (ref "C20") (pin "2") (pinfunction "2_2") (pintype "passive"))
      (node (ref "C21") (pin "2") (pinfunction "2_2") (pintype "passive"))
      (node (ref "C8") (pin "2") (pinfunction "2_2") (pintype "passive"))
      (node (ref "P11") (pin "1") (pinfunction "1_1") (pintype "passive"))
      (node (ref "P6") (pin "1") (pinfunction "1_1") (pintype "passive"))
      (node (ref "P6") (pin "2") (pinfunction "2_2") (pintype "passive"))
      (node (ref "P6") (pin "3") (pinfunction "3_3") (pintype "passive"))
      (node (ref "P6") (pin "4") (pinfunction "4_4") (pintype "passive"))
      (node (ref "P9") (pin "7") (pinfunction "7_7") (pintype "passive"))
      (node (ref "R1") (pin "1") (pintype "passive"))
      (node (ref "R18") (pin "2") (pinfunction "2_2") (pintype "passive"))
      (node (ref "R2") (pin "1") (pintype "passive"))
      (node (ref "U2") (pin "25") (pinfunction "VDD_VIO_1_25") (pintype "power_in"))
      (node (ref "U2") (pin "48") (pinfunction "VDD_VIO_3_48") (pintype "power_in"))
    )
    (net (code "65") (name "unconnected-(P5-D+-PadA6)") (class "Default")
      (node (ref "P5") (pin "A6") (pinfunction "D+_A6") (pintype "bidirectional+no_connect"))
    )
    (net (code "66") (name "unconnected-(P5-D+-PadB6)") (class "Default")
      (node (ref "P5") (pin "B6") (pinfunction "D+_B6") (pintype "bidirectional+no_connect"))
    )
    (net (code "67") (name "unconnected-(P5-D--PadA7)") (class "Default")
      (node (ref "P5") (pin "A7") (pinfunction "D-_A7") (pintype "bidirectional+no_connect"))
    )
    (net (code "68") (name "unconnected-(P5-D--PadB7)") (class "Default")
      (node (ref "P5") (pin "B7") (pinfunction "D-_B7") (pintype "bidirectional+no_connect"))
    )
    (net (code "69") (name "unconnected-(P5-RFU1-PadA8)") (class "Default")
      (node (ref "P5") (pin "A8") (pinfunction "RFU1_A8") (pintype "bidirectional+no_connect"))
    )
    (net (code "70") (name "unconnected-(P5-RFU1-PadB8)") (class "Default")
      (node (ref "P5") (pin "B8") (pinfunction "RFU1_B8") (pintype "bidirectional+no_connect"))
    )
    (net (code "71") (name "unconnected-(U1-NC.-Pad2)") (class "Default")
      (node (ref "U1") (pin "2") (pinfunction "NC._2") (pintype "passive"))
    )
    (net (code "72") (name "unconnected-(U1-NC.-Pad3)") (class "Default")
      (node (ref "U1") (pin "3") (pinfunction "NC._3") (pintype "passive"))
    )
  )
)
